# ESC.net
KiCad netlist of a schematic drawn in Altium Designer
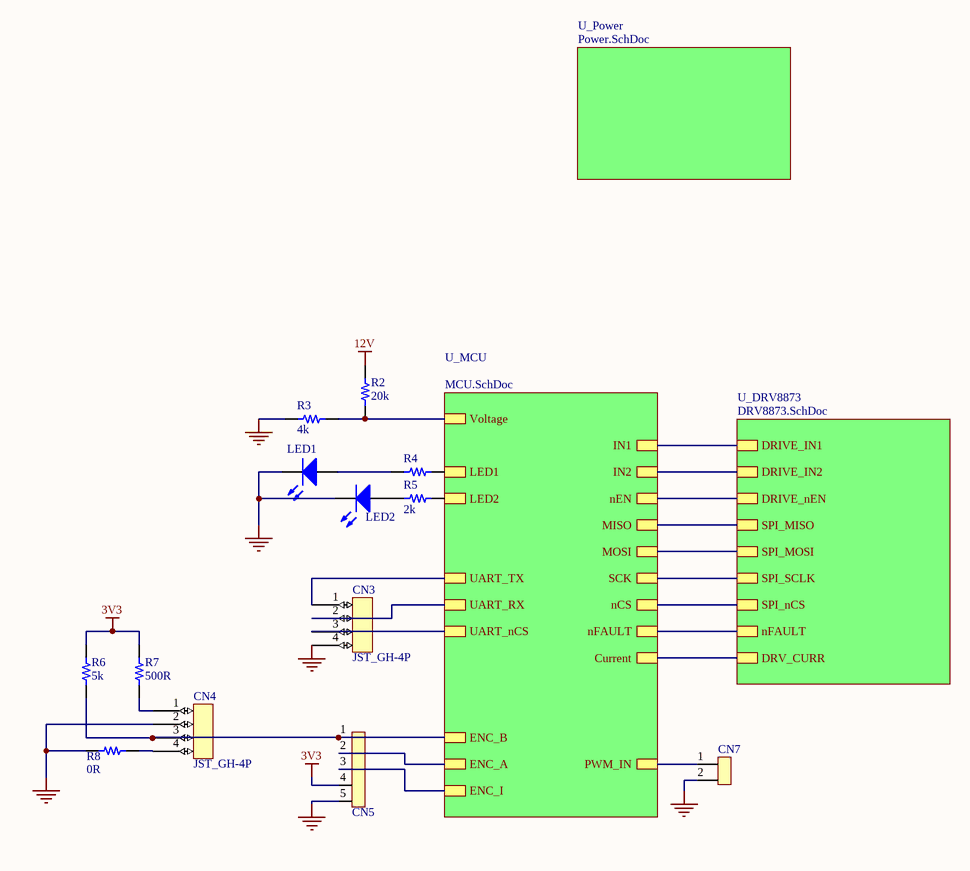
[diagram p0: ESC.SchDoc]

(export (version "E")
  (design (tool "Eeschema 10.0.6"))
  (components
    (comp (ref "CN3")
      (value "JST_GH-4P")
      (footprint "JST_GH-4P")
      (libsource (lib "Parts") (part "JST_GH-4P"))
    )
    (comp (ref "CN4")
      (value "JST_GH-4P")
      (footprint "JST_GH-4P")
      (libsource (lib "Parts") (part "JST_GH-4P"))
    )
    (comp (ref "CN5")
      (value "5P-2.5mm")
      (footprint "5-Pin-Header")
      (libsource (lib "Parts") (part "5P-2.5mm"))
    )
    (comp (ref "CN7") (value "2P-2.5mm") (footprint "2.5mm-2P") (libsource (lib "Parts") (part "2P-2.5mm")))
    (comp (ref "LED1") (value "LED") (footprint "0805-LED") (libsource (lib "Parts") (part "LED")))
    (comp (ref "LED2") (value "LED") (footprint "0805-LED") (libsource (lib "Parts") (part "LED")))
    (comp (ref "R2") (value "20k") (footprint "0805 - duplicate") (libsource (lib "Parts") (part "Resistor")))
    (comp (ref "R3") (value "4k") (footprint "0805 - duplicate") (libsource (lib "Parts") (part "Resistor")))
    (comp (ref "R4") (value "4k") (footprint "0805 - duplicate") (libsource (lib "Parts") (part "Resistor")))
    (comp (ref "R5") (value "2k") (footprint "0805 - duplicate") (libsource (lib "Parts") (part "Resistor")))
    (comp (ref "R6") (value "5k") (footprint "0805 - duplicate") (libsource (lib "Parts") (part "Resistor")))
    (comp (ref "R7")
      (value "500R")
      (footprint "0805 - duplicate")
      (libsource (lib "Parts") (part "Resistor"))
    )
    (comp (ref "R8") (value "0R") (footprint "0805 - duplicate") (libsource (lib "Parts") (part "Resistor")))
  )
  (nets
    (net (code "5") (name "/ENC_A") (class "Default") (node (ref "CN5") (pin "2") (pintype "passive")))
    (net (code "6") (name "/ENC_B") (class "Default")
      (node (ref "CN4") (pin "3") (pintype "bidirectional"))
      (node (ref "CN5") (pin "1") (pintype "passive"))
      (node (ref "R6") (pin "2") (pinfunction "2_2") (pintype "passive"))
    )
    (net (code "7") (name "/ENC_I") (class "Default") (node (ref "CN5") (pin "3") (pintype "passive")))
    (net (code "8") (name "/LED1") (class "Default")
      (node (ref "R4") (pin "1") (pinfunction "1_1") (pintype "passive"))
    )
    (net (code "9") (name "/LED2") (class "Default")
      (node (ref "R5") (pin "1") (pinfunction "1_1") (pintype "passive"))
    )
    (net (code "12") (name "/PWM_IN") (class "Default") (node (ref "CN7") (pin "1") (pintype "passive")))
    (net (code "15") (name "/UART_RX") (class "Default")
      (node (ref "CN3") (pin "2") (pintype "bidirectional"))
    )
    (net (code "16") (name "/UART_TX") (class "Default")
      (node (ref "CN3") (pin "1") (pintype "bidirectional"))
    )
    (net (code "17") (name "/UART_nCS") (class "Default")
      (node (ref "CN3") (pin "3") (pintype "bidirectional"))
    )
    (net (code "18") (name "/Voltage") (class "Default")
      (node (ref "R2") (pin "1") (pinfunction "1_1") (pintype "passive"))
      (node (ref "R3") (pin "1") (pinfunction "1_1") (pintype "passive"))
    )
    (net (code "20") (name "3V3") (class "Default")
      (node (ref "CN5") (pin "4") (pintype "passive"))
      (node (ref "R6") (pin "1") (pinfunction "1_1") (pintype "passive"))
      (node (ref "R7") (pin "1") (pinfunction "1_1") (pintype "passive"))
    )
    (net (code "21") (name "12V") (class "Default")
      (node (ref "R2") (pin "2") (pinfunction "2_2") (pintype "passive"))
    )
    (net (code "22") (name "GND") (class "Default")
      (node (ref "CN3") (pin "4") (pintype "bidirectional"))
      (node (ref "CN4") (pin "2") (pintype "bidirectional"))
      (node (ref "CN5") (pin "5") (pintype "passive"))
      (node (ref "CN7") (pin "2") (pintype "passive"))
      (node (ref "LED1") (pin "2") (pinfunction "K_2") (pintype "passive"))
      (node (ref "LED2") (pin "2") (pinfunction "K_2") (pintype "passive"))
      (node (ref "R3") (pin "2") (pinfunction "2_2") (pintype "passive"))
      (node (ref "R8") (pin "1") (pinfunction "1_1") (pintype "passive"))
    )
    (net (code "23") (name "Net-(CN4-Pad1)") (class "Default")
      (node (ref "CN4") (pin "1") (pintype "bidirectional"))
      (node (ref "R7") (pin "2") (pinfunction "2_2") (pintype "passive"))
    )
    (net (code "24") (name "Net-(CN4-Pad4)") (class "Default")
      (node (ref "CN4") (pin "4") (pintype "bidirectional"))
      (node (ref "R8") (pin "2") (pinfunction "2_2") (pintype "passive"))
    )
    (net (code "25") (name "Net-(LED1-A)") (class "Default")
      (node (ref "LED1") (pin "1") (pinfunction "A_1") (pintype "passive"))
      (node (ref "R4") (pin "2") (pinfunction "2_2") (pintype "passive"))
    )
    (net (code "26") (name "Net-(LED2-A)") (class "Default")
      (node (ref "LED2") (pin "1") (pinfunction "A_1") (pintype "passive"))
      (node (ref "R5") (pin "2") (pinfunction "2_2") (pintype "passive"))
    )
  )
)
